# Power.net
KiCad netlist of a schematic drawn in Altium Designer
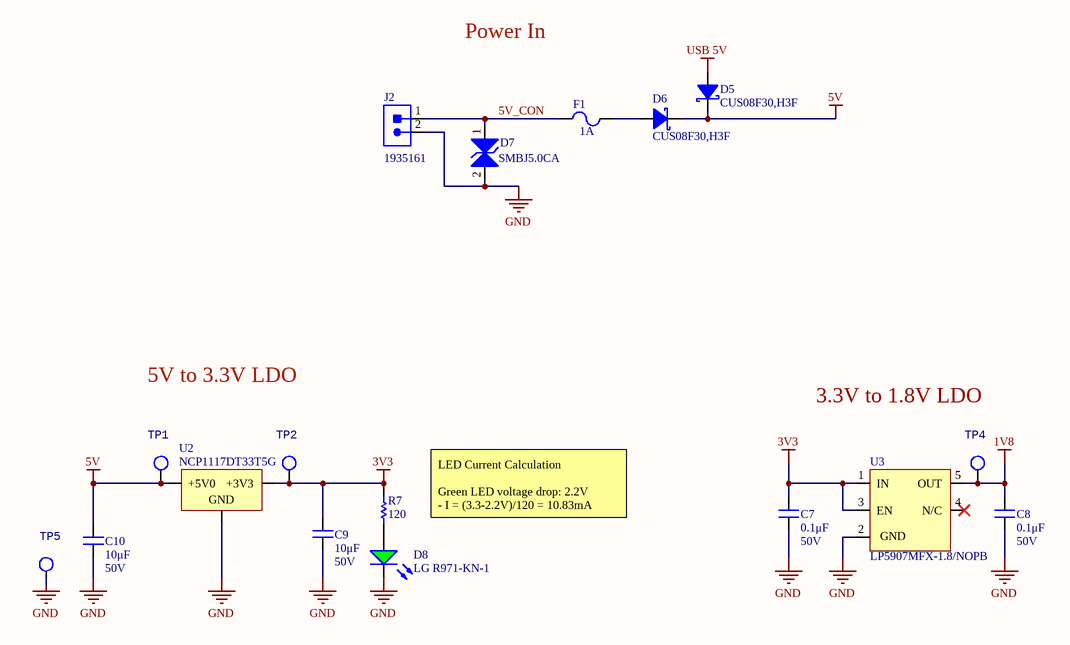
[diagram p0: Power.SchDoc]

(export (version "E")
  (design (tool "Eeschema 10.0.6"))
  (components
    (comp (ref "C7")
      (value "0.1μF")
      (footprint "CAP2012")
      (description "CAP CER 0.1UF 50V X7R 0805")
      (fields
        (field (name "TOLERANCE") "10%")
        (field (name "VOLTAGE RATING") "50V")
        (field (name "Comment") "CAP_0.1uF_50V_0805")
      )
      (libsource (lib "UWRT_Schematic_Library_2020") (part "CAP_0.1uF_50V_0805"))
    )
    (comp (ref "C8")
      (value "0.1μF")
      (footprint "CAP2012")
      (description "CAP CER 0.1UF 50V X7R 0805")
      (fields
        (field (name "TOLERANCE") "10%")
        (field (name "VOLTAGE RATING") "50V")
        (field (name "Comment") "CAP_0.1uF_50V_0805")
      )
      (libsource (lib "UWRT_Schematic_Library_2020") (part "CAP_0.1uF_50V_0805"))
    )
    (comp (ref "C9")
      (value "10μF")
      (footprint "CAP1206")
      (description "CAP CER 10UF 50V X5R 1206")
      (fields (field (name "VOLTAGE RATING") "50V") (field (name "Comment") "CAP_10uF_50V_1206"))
      (libsource (lib "UWRT_Schematic_Library_2020") (part "CAP_10uF_50V_1206"))
    )
    (comp (ref "C10")
      (value "10μF")
      (footprint "CAP1206")
      (description "CAP CER 10UF 50V X5R 1206")
      (fields (field (name "VOLTAGE RATING") "50V") (field (name "Comment") "CAP_10uF_50V_1206"))
      (libsource (lib "UWRT_Schematic_Library_2020") (part "CAP_10uF_50V_1206"))
    )
    (comp (ref "D5")
      (value "DIO_SCHOTTKY_30V_800mA")
      (footprint "SOD-323_UNIDIR")
      (description "DIODE SCHOTTKY 30V 800MA USC")
      (fields (field (name "MANUFACTURER PART NUMBER 1") "CUS08F30,H3F"))
      (libsource (lib "UWRT_Schematic_Library_2020") (part "DIO_SCHOTTKY_30V_800mA"))
    )
    (comp (ref "D6")
      (value "DIO_SCHOTTKY_30V_800mA")
      (footprint "SOD-323_UNIDIR")
      (description "DIODE SCHOTTKY 30V 800MA USC")
      (fields (field (name "MANUFACTURER PART NUMBER 1") "CUS08F30,H3F"))
      (libsource (lib "UWRT_Schematic_Library_2020") (part "DIO_SCHOTTKY_30V_800mA"))
    )
    (comp (ref "D7")
      (value "TVS_DIODE_BIDIR_5V")
      (footprint "TVS_DIODE_BIDIRECTIONAL")
      (description "TVS DIODE 5V 9.2V DO214AA")
      (fields (field (name "MANUFACTURER PART NUMBER 1") "SMBJ5.0CA"))
      (libsource (lib "UWRT_Schematic_Library_2020") (part "TVS_DIODE_BIDIR_5V"))
    )
    (comp (ref "D8")
      (value "LG R971-KN-1")
      (footprint "LED_0805_GREEN")
      (description "LED GREEN DIFFUSED 0805 SMD")
      (libsource (lib "UWRT_Schematic_Library_2020") (part "DIO_LED_G"))
    )
    (comp (ref "F1")
      (value "FUSE_1A_1206")
      (footprint "FUSE_1206")
      (description "FUSE BOARD MOUNT 1A 125VAC 63VDC")
      (fields (field (name "CURRENT RATING") "1A"))
      (libsource (lib "UWRT_Schematic_Library_2020") (part "FUSE_1A_1206"))
    )
    (comp (ref "J2")
      (value "1935161")
      (footprint "1935161")
      (description "TERM BLK 2POS SIDE ENTRY 5MM")
      (fields (field (name "MANUFACTURER PART NUMBER 1") "1935161") (field (name "VOLTAGE") "300V"))
      (libsource (lib "UWRT_Schematic_Library_2020") (part "CON_2M_TERM"))
    )
    (comp (ref "R7")
      (value "120")
      (footprint "RESC0603(1608)_N")
      (description "RES SMD 120 OHM 5% 1/10W 0603")
      (fields (field (name "TOLERANCE") "5%") (field (name "Comment") "RES_120R_0603"))
      (libsource (lib "UWRT_Schematic_Library_2020") (part "RES_120R_0603"))
    )
    (comp (ref "TP1")
      (value "TESTPOINT_LOOP")
      (footprint "TESTPOINT_LOOP")
      (description "PC TEST POINT MINIATURE WHITE")
      (libsource (lib "UWRT_Schematic_Library_2020") (part "TESTPOINT_LOOP"))
    )
    (comp (ref "TP2")
      (value "TESTPOINT_LOOP")
      (footprint "TESTPOINT_LOOP")
      (description "PC TEST POINT MINIATURE WHITE")
      (libsource (lib "UWRT_Schematic_Library_2020") (part "TESTPOINT_LOOP"))
    )
    (comp (ref "TP4")
      (value "TESTPOINT_LOOP")
      (footprint "TESTPOINT_LOOP")
      (description "PC TEST POINT MINIATURE WHITE")
      (libsource (lib "UWRT_Schematic_Library_2020") (part "TESTPOINT_LOOP"))
    )
    (comp (ref "TP5")
      (value "TESTPOINT_LOOP")
      (footprint "TESTPOINT_LOOP")
      (description "PC TEST POINT MINIATURE WHITE")
      (libsource (lib "UWRT_Schematic_Library_2020") (part "TESTPOINT_LOOP"))
    )
    (comp (ref "U2")
      (value "5V0_3V3_LDO")
      (footprint "VOLTAGE_REGULATOR")
      (description "IC REG LINEAR 3.3V 1A DPAK")
      (fields (field (name "MANUFACTURER PART NUMBER 1") "NCP1117DT33T5G"))
      (libsource (lib "UWRT_Schematic_Library_2020") (part "5V0_3V3_LDO"))
    )
    (comp (ref "U3")
      (value "LDO_1.8V_250mA")
      (footprint "UWRT_Footprint_Library_2020:LP5907MFX-1.8/NOPB")
      (description "IC REG LINEAR 1.8V 250MA SOT23-5")
      (fields (field (name "MANUFACTURER PART NUMBER 1") "LP5907MFX-1.8/NOPB"))
      (libsource (lib "UWRT_Schematic_Library_2020") (part "LDO_1.8V_250mA"))
    )
  )
  (nets
    (net (code "1") (name "/5V_CON") (class "Default")
      (node (ref "D7") (pin "1") (pinfunction "1_1") (pintype "passive"))
      (node (ref "F1") (pin "1") (pinfunction "1_1") (pintype "passive"))
      (node (ref "J2") (pin "1") (pinfunction "1_1") (pintype "passive"))
    )
    (net (code "2") (name "1V8") (class "Default")
      (node (ref "C8") (pin "2") (pinfunction "2_2") (pintype "passive"))
      (node (ref "TP4") (pin "1") (pintype "passive"))
      (node (ref "U3") (pin "5") (pinfunction "OUT_5") (pintype "passive"))
    )
    (net (code "3") (name "3V3") (class "Default")
      (node (ref "C7") (pin "2") (pinfunction "2_2") (pintype "passive"))
      (node (ref "C9") (pin "2") (pinfunction "2_2") (pintype "passive"))
      (node (ref "R7") (pin "2") (pinfunction "2_2") (pintype "passive"))
      (node (ref "TP2") (pin "1") (pintype "passive"))
      (node (ref "U2") (pin "2") (pinfunction "+3V3_2") (pintype "passive"))
      (node (ref "U3") (pin "1") (pinfunction "IN_1") (pintype "passive"))
      (node (ref "U3") (pin "3") (pinfunction "EN_3") (pintype "passive"))
    )
    (net (code "4") (name "5V") (class "Default")
      (node (ref "C10") (pin "2") (pinfunction "2_2") (pintype "passive"))
      (node (ref "D5") (pin "2") (pinfunction "Cathode_2") (pintype "passive"))
      (node (ref "D6") (pin "2") (pinfunction "Cathode_2") (pintype "passive"))
      (node (ref "TP1") (pin "1") (pintype "passive"))
      (node (ref "U2") (pin "3") (pinfunction "+5V0_3") (pintype "passive"))
    )
    (net (code "5") (name "GND") (class "Default")
      (node (ref "C10") (pin "1") (pinfunction "1_1") (pintype "passive"))
      (node (ref "C7") (pin "1") (pinfunction "1_1") (pintype "passive"))
      (node (ref "C8") (pin "1") (pinfunction "1_1") (pintype "passive"))
      (node (ref "C9") (pin "1") (pinfunction "1_1") (pintype "passive"))
      (node (ref "D7") (pin "2") (pinfunction "2_2") (pintype "passive"))
      (node (ref "D8") (pin "2") (pinfunction "K_2") (pintype "passive"))
      (node (ref "J2") (pin "2") (pinfunction "2_2") (pintype "passive"))
      (node (ref "TP5") (pin "1") (pintype "passive"))
      (node (ref "U2") (pin "1") (pinfunction "GND_1") (pintype "passive"))
      (node (ref "U3") (pin "2") (pinfunction "GND_2") (pintype "passive"))
    )
    (net (code "6") (name "Net-(D6-Anode)") (class "Default")
      (node (ref "D6") (pin "1") (pinfunction "Anode_1") (pintype "passive"))
      (node (ref "F1") (pin "2") (pinfunction "2_2") (pintype "passive"))
    )
    (net (code "7") (name "Net-(D8-A)") (class "Default")
      (node (ref "D8") (pin "1") (pinfunction "A_1") (pintype "passive"))
      (node (ref "R7") (pin "1") (pinfunction "1_1") (pintype "passive"))
    )
    (net (code "8") (name "USB 5V") (class "Default")
      (node (ref "D5") (pin "1") (pinfunction "Anode_1") (pintype "passive"))
    )
    (net (code "9") (name "unconnected-(U3-N{slash}C-Pad4)") (class "Default")
      (node (ref "U3") (pin "4") (pinfunction "N/C_4") (pintype "passive+no_connect"))
    )
  )
)
